# configure.net
KiCad netlist of a schematic drawn in Altium Designer
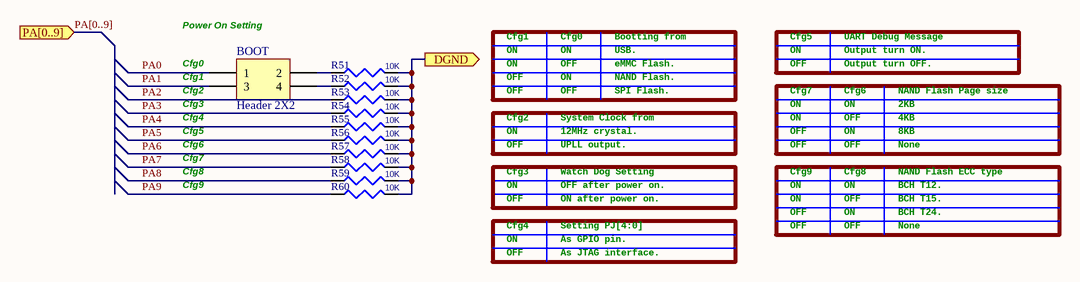
[diagram p0: configure.SchDoc]

(export (version "E")
  (design (tool "Eeschema 10.0.6"))
  (components
    (comp (ref "BOOT")
      (value "Header 2X2")
      (footprint "HDR2X2")
      (description "Header, 2-Pin, Dual row")
      (fields (field (name "PUBLISHER") "Altium Limited"))
      (libsource (lib "Miscellaneous Connectors") (part "Header 2X2"))
    )
    (comp (ref "R51") (value "10K") (footprint "0603R") (libsource (lib "*") (part "R_Dup1")))
    (comp (ref "R52") (value "10K") (footprint "0603R") (libsource (lib "*") (part "R_Dup1")))
    (comp (ref "R53") (value "10K") (footprint "0603R") (libsource (lib "*") (part "R_Dup1")))
    (comp (ref "R54") (value "10K") (footprint "0603R") (libsource (lib "*") (part "R_Dup1")))
    (comp (ref "R55") (value "10K") (footprint "0603R") (libsource (lib "*") (part "R_Dup1")))
    (comp (ref "R56") (value "10K") (footprint "0603R") (libsource (lib "*") (part "R_Dup1")))
    (comp (ref "R57") (value "10K") (footprint "0603R") (libsource (lib "*") (part "R_Dup1")))
    (comp (ref "R58") (value "10K") (footprint "0603R") (libsource (lib "*") (part "R_Dup1")))
    (comp (ref "R59") (value "10K") (footprint "0603R") (libsource (lib "*") (part "R_Dup1")))
    (comp (ref "R60") (value "10K") (footprint "0603R") (libsource (lib "*") (part "R_Dup1")))
  )
  (nets
    (net (code "1") (name "/DGND") (class "Default")
      (node (ref "R51") (pin "2") (pinfunction "2_2") (pintype "passive"))
      (node (ref "R52") (pin "2") (pinfunction "2_2") (pintype "passive"))
      (node (ref "R53") (pin "2") (pinfunction "2_2") (pintype "passive"))
      (node (ref "R54") (pin "2") (pinfunction "2_2") (pintype "passive"))
      (node (ref "R55") (pin "2") (pinfunction "2_2") (pintype "passive"))
      (node (ref "R56") (pin "2") (pinfunction "2_2") (pintype "passive"))
      (node (ref "R57") (pin "2") (pinfunction "2_2") (pintype "passive"))
      (node (ref "R58") (pin "2") (pinfunction "2_2") (pintype "passive"))
      (node (ref "R59") (pin "2") (pinfunction "2_2") (pintype "passive"))
      (node (ref "R60") (pin "2") (pinfunction "2_2") (pintype "passive"))
    )
    (net (code "2") (name "/PA0") (class "Default")
      (node (ref "BOOT") (pin "1") (pinfunction "1_1") (pintype "passive"))
    )
    (net (code "3") (name "/PA1") (class "Default")
      (node (ref "BOOT") (pin "3") (pinfunction "3_3") (pintype "passive"))
    )
    (net (code "4") (name "/PA2") (class "Default")
      (node (ref "R53") (pin "1") (pinfunction "1_1") (pintype "passive"))
    )
    (net (code "5") (name "/PA3") (class "Default")
      (node (ref "R54") (pin "1") (pinfunction "1_1") (pintype "passive"))
    )
    (net (code "6") (name "/PA4") (class "Default")
      (node (ref "R55") (pin "1") (pinfunction "1_1") (pintype "passive"))
    )
    (net (code "7") (name "/PA5") (class "Default")
      (node (ref "R56") (pin "1") (pinfunction "1_1") (pintype "passive"))
    )
    (net (code "8") (name "/PA6") (class "Default")
      (node (ref "R57") (pin "1") (pinfunction "1_1") (pintype "passive"))
    )
    (net (code "9") (name "/PA7") (class "Default")
      (node (ref "R58") (pin "1") (pinfunction "1_1") (pintype "passive"))
    )
    (net (code "10") (name "/PA8") (class "Default")
      (node (ref "R59") (pin "1") (pinfunction "1_1") (pintype "passive"))
    )
    (net (code "11") (name "/PA9") (class "Default")
      (node (ref "R60") (pin "1") (pinfunction "1_1") (pintype "passive"))
    )
    (net (code "13") (name "Net-(BOOT-Pad2)") (class "Default")
      (node (ref "BOOT") (pin "2") (pinfunction "2_2") (pintype "passive"))
      (node (ref "R51") (pin "1") (pinfunction "1_1") (pintype "passive"))
    )
    (net (code "14") (name "Net-(BOOT-Pad4)") (class "Default")
      (node (ref "BOOT") (pin "4") (pinfunction "4_4") (pintype "passive"))
      (node (ref "R52") (pin "1") (pinfunction "1_1") (pintype "passive"))
    )
  )
)
